# SparkFun_ProtoSnap-LilyTwinkle.net
KiCad netlist of a schematic drawn in EAGLE
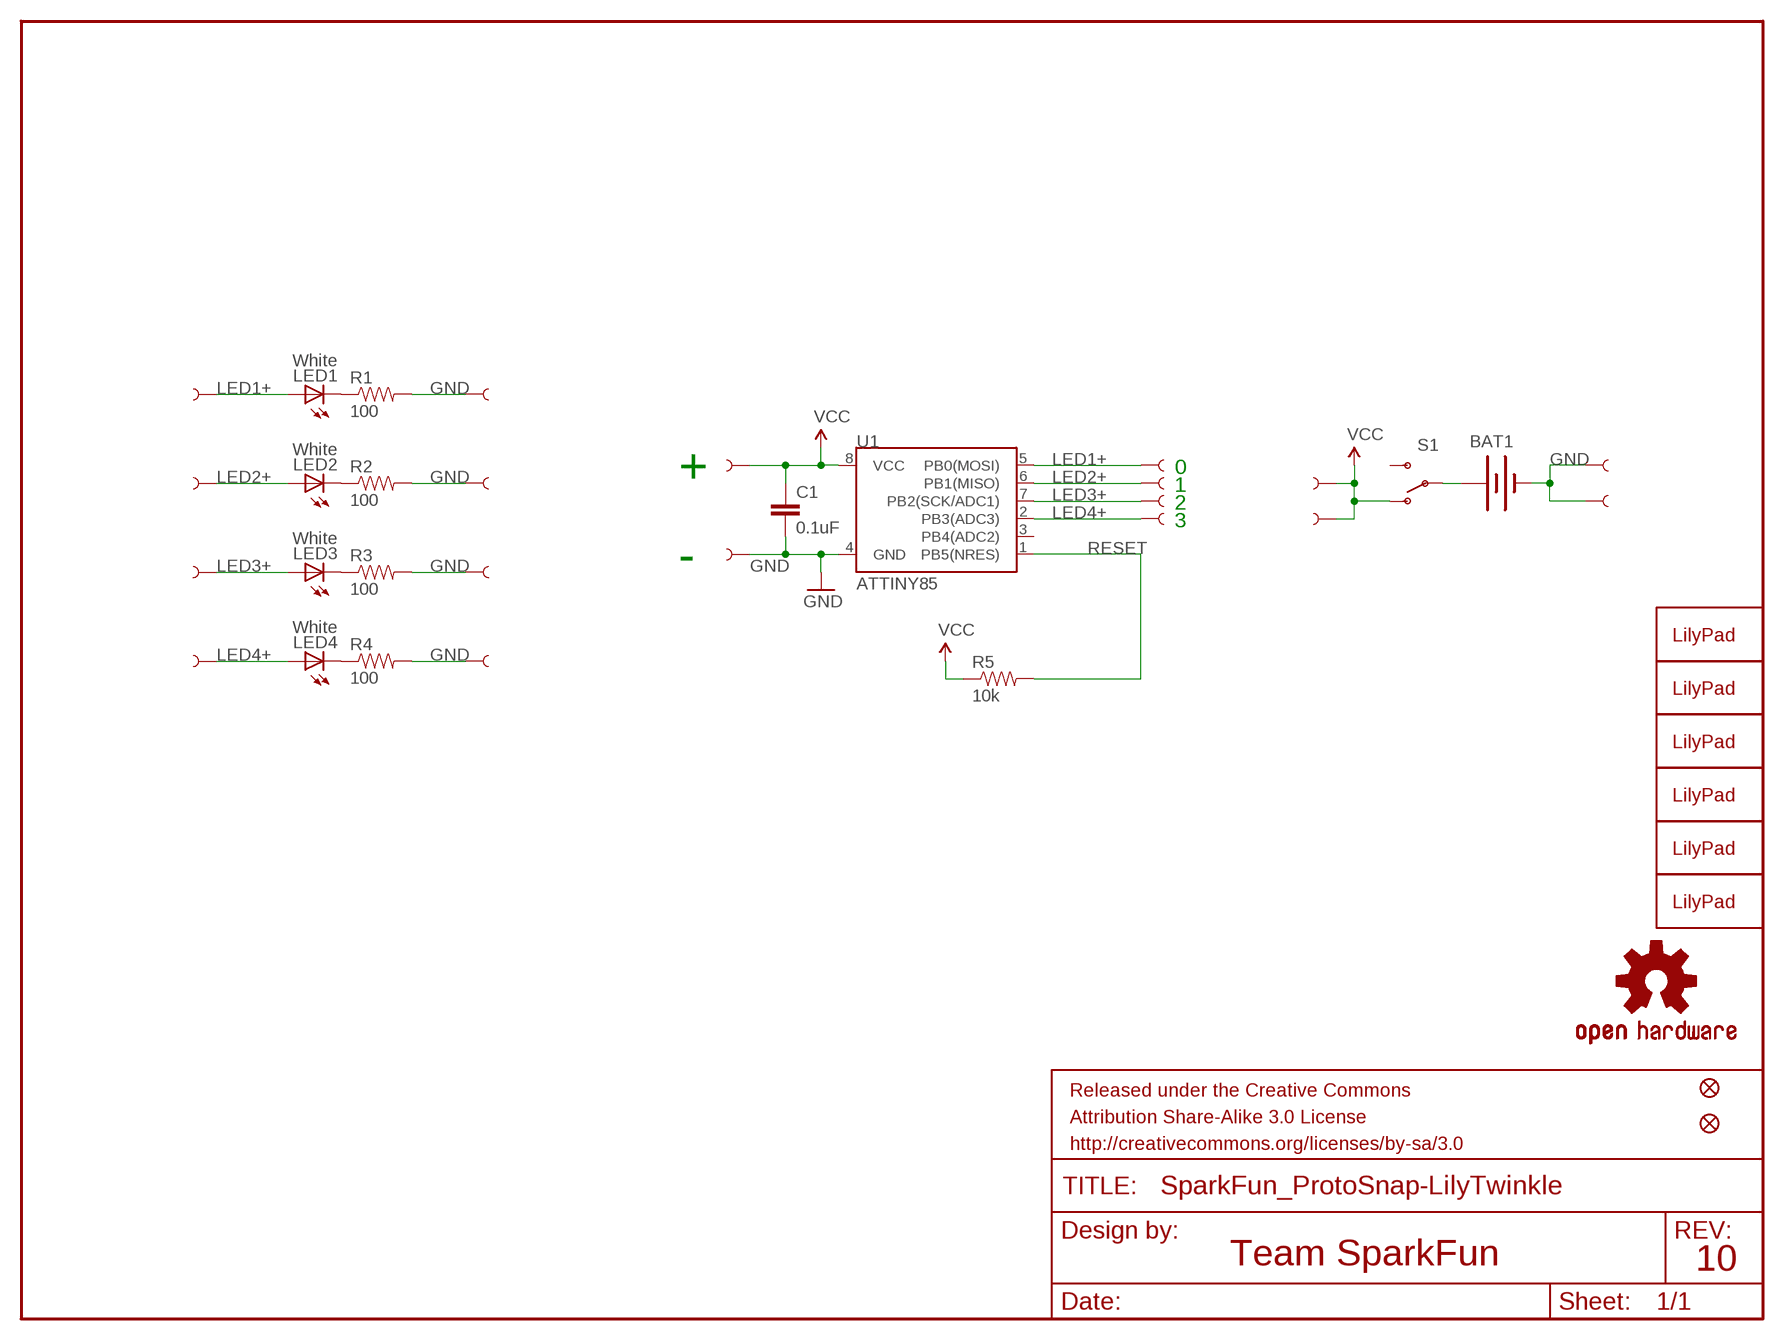
[diagram p0: schematic, sheet 1]

(export (version "E")
  (design (tool "Eeschema 10.0.6"))
  (components
    (comp (ref "1_U$2")
      (value "SEWTAP6")
      (footprint "eagle-import:PETAL-SMALL-2SIDE")
      (libsource (lib "eagle-import") (part "SEWTAP6"))
    )
    (comp (ref "1_U$3")
      (value "SEWTAP6")
      (footprint "eagle-import:PETAL-SMALL-2SIDE")
      (libsource (lib "eagle-import") (part "SEWTAP6"))
    )
    (comp (ref "1_U$4")
      (value "SEWTAP6")
      (footprint "eagle-import:PETAL-SMALL-2SIDE")
      (libsource (lib "eagle-import") (part "SEWTAP6"))
    )
    (comp (ref "1_U$5")
      (value "SEWTAP6")
      (footprint "eagle-import:PETAL-SMALL-2SIDE")
      (libsource (lib "eagle-import") (part "SEWTAP6"))
    )
    (comp (ref "1_U$6")
      (value "SEWTAP6")
      (footprint "eagle-import:PETAL-SMALL-2SIDE")
      (libsource (lib "eagle-import") (part "SEWTAP6"))
    )
    (comp (ref "1_U$7")
      (value "SEWTAP6")
      (footprint "eagle-import:PETAL-SMALL-2SIDE")
      (libsource (lib "eagle-import") (part "SEWTAP6"))
    )
    (comp (ref "3_LED+")
      (value "SEWTAP6")
      (footprint "eagle-import:PETAL-SMALL")
      (libsource (lib "eagle-import") (part "3_LilyPad-Wearables_SEWTAP4"))
    )
    (comp (ref "3_LED-")
      (value "SEWTAP6")
      (footprint "eagle-import:PETAL-SMALL")
      (libsource (lib "eagle-import") (part "SEWTAP2SIDE"))
    )
    (comp (ref "4_LED+")
      (value "SEWTAP6")
      (footprint "eagle-import:PETAL-SMALL")
      (libsource (lib "eagle-import") (part "4_LilyPad-Wearables_SEWTAP4"))
    )
    (comp (ref "4_LED-")
      (value "SEWTAP6")
      (footprint "eagle-import:PETAL-SMALL")
      (libsource (lib "eagle-import") (part "4_LilyPad-Wearables_SEWTAP2SIDE"))
    )
    (comp (ref "5_LED+")
      (value "SEWTAP6")
      (footprint "eagle-import:PETAL-SMALL")
      (libsource (lib "eagle-import") (part "5_LilyPad-Wearables_SEWTAP4"))
    )
    (comp (ref "5_LED-")
      (value "SEWTAP6")
      (footprint "eagle-import:PETAL-SMALL")
      (libsource (lib "eagle-import") (part "5_LilyPad-Wearables_SEWTAP2SIDE"))
    )
    (comp (ref "6_LED+")
      (value "SEWTAP6")
      (footprint "eagle-import:PETAL-SMALL")
      (libsource (lib "eagle-import") (part "6_LilyPad-Wearables_SEWTAP4"))
    )
    (comp (ref "6_LED-")
      (value "SEWTAP6")
      (footprint "eagle-import:PETAL-SMALL")
      (libsource (lib "eagle-import") (part "6_LilyPad-Wearables_SEWTAP2SIDE"))
    )
    (comp (ref "B1+")
      (value "SEWTAP6")
      (footprint "eagle-import:PETAL-SMALL-2SIDE")
      (libsource (lib "eagle-import") (part "2_LilyPad-Wearables_SEWTAP6"))
    )
    (comp (ref "B1-")
      (value "SEWTAP6")
      (footprint "eagle-import:PETAL-SMALL-2SIDE")
      (libsource (lib "eagle-import") (part "2_LilyPad-Wearables_SEWTAP6"))
    )
    (comp (ref "B2+")
      (value "SEWTAP6")
      (footprint "eagle-import:PETAL-SMALL-2SIDE")
      (libsource (lib "eagle-import") (part "2_LilyPad-Wearables_SEWTAP6"))
    )
    (comp (ref "B2-")
      (value "SEWTAP6")
      (footprint "eagle-import:PETAL-SMALL-2SIDE")
      (libsource (lib "eagle-import") (part "2_LilyPad-Wearables_SEWTAP6"))
    )
    (comp (ref "BAT1")
      (value "BATTERY20MM_4LEGS")
      (footprint "eagle-import:BATTCON_20MM_4LEGS")
      (libsource (lib "eagle-import") (part "BATTERY20MM_4LEGS"))
    )
    (comp (ref "BATT_LOGO")
      (value "LOGO-LPLP")
      (footprint "eagle-import:LOGO-LILYPAD")
      (libsource (lib "eagle-import") (part "LOGO-LPLP"))
    )
    (comp (ref "BATT_OHS")
      (value "OSHW-LOGOS")
      (footprint "eagle-import:OSHW-LOGO-S")
      (libsource (lib "eagle-import") (part "OSHW-LOGOS"))
    )
    (comp (ref "C1")
      (value "0.1uF")
      (footprint "eagle-import:0402-CAP")
      (libsource (lib "eagle-import") (part ".1UF-CER"))
    )
    (comp (ref "FRAME1")
      (value "FRAME-LETTER")
      (footprint "eagle-import:CREATIVE_COMMONS")
      (libsource (lib "eagle-import") (part "FRAME-LETTER"))
    )
    (comp (ref "JP1")
      (value "FIDUCIALUFIDUCIAL")
      (footprint "eagle-import:MICRO-FIDUCIAL")
      (libsource (lib "eagle-import") (part "FIDUCIALUFIDUCIAL"))
    )
    (comp (ref "JP2")
      (value "FIDUCIALUFIDUCIAL")
      (footprint "eagle-import:MICRO-FIDUCIAL")
      (libsource (lib "eagle-import") (part "FIDUCIALUFIDUCIAL"))
    )
    (comp (ref "LED1")
      (value "White")
      (footprint "eagle-import:LED-1206")
      (libsource (lib "eagle-import") (part "LED-WHITE"))
    )
    (comp (ref "LED1_LOGO")
      (value "LOGO-LPL")
      (footprint "eagle-import:LOGO-L")
      (libsource (lib "eagle-import") (part "LOGO-LPL"))
    )
    (comp (ref "LED2")
      (value "White")
      (footprint "eagle-import:LED-1206")
      (libsource (lib "eagle-import") (part "LED-WHITE"))
    )
    (comp (ref "LED2_LOGO")
      (value "LOGO-LPL")
      (footprint "eagle-import:LOGO-L")
      (libsource (lib "eagle-import") (part "LOGO-LPL"))
    )
    (comp (ref "LED3")
      (value "White")
      (footprint "eagle-import:LED-1206")
      (libsource (lib "eagle-import") (part "LED-WHITE"))
    )
    (comp (ref "LED3_LOGO")
      (value "LOGO-LPL")
      (footprint "eagle-import:LOGO-L")
      (libsource (lib "eagle-import") (part "LOGO-LPL"))
    )
    (comp (ref "LED4")
      (value "White")
      (footprint "eagle-import:LED-1206")
      (libsource (lib "eagle-import") (part "LED-WHITE"))
    )
    (comp (ref "LED4_LOGO")
      (value "LOGO-LPL")
      (footprint "eagle-import:LOGO-L")
      (libsource (lib "eagle-import") (part "LOGO-LPL"))
    )
    (comp (ref "R1")
      (value "100")
      (footprint "eagle-import:0603-RES")
      (libsource (lib "eagle-import") (part "6_SparkFun_RESISTOR0603-RES"))
    )
    (comp (ref "R2")
      (value "100")
      (footprint "eagle-import:0603-RES")
      (libsource (lib "eagle-import") (part "5_SparkFun_RESISTOR0603-RES"))
    )
    (comp (ref "R3")
      (value "100")
      (footprint "eagle-import:0603-RES")
      (libsource (lib "eagle-import") (part "RESISTOR0603-RES"))
    )
    (comp (ref "R4")
      (value "100")
      (footprint "eagle-import:0603-RES")
      (libsource (lib "eagle-import") (part "4_SparkFun_RESISTOR0603-RES"))
    )
    (comp (ref "R5")
      (value "10k")
      (footprint "eagle-import:0402-RES")
      (libsource (lib "eagle-import") (part "10K-1%RES-00824"))
    )
    (comp (ref "S1")
      (value "SWITCH-SPDTSMD")
      (footprint "eagle-import:AYZ0202")
      (libsource (lib "eagle-import") (part "SWITCH-SPDTSMD"))
    )
    (comp (ref "TINY_LOGO")
      (value "LOGO-LPL")
      (footprint "eagle-import:LOGO-L")
      (libsource (lib "eagle-import") (part "LOGO-LPL"))
    )
    (comp (ref "U1")
      (value "ATTINY85")
      (footprint "eagle-import:SO08-EIAJ")
      (libsource (lib "eagle-import") (part "ATTINY45TINY85-20-SMT"))
    )
  )
  (nets
    (net (code "1") (name "/LED1+") (class "Default")
      (node (ref "1_U$7") (pin "1") (pinfunction "1_1") (pintype "bidirectional"))
      (node (ref "6_LED+") (pin "1") (pinfunction "1_1") (pintype "bidirectional"))
      (node (ref "LED1") (pin "A") (pinfunction "A_A") (pintype "passive"))
      (node (ref "U1") (pin "5") (pinfunction "PB0(MOSI)_5") (pintype "bidirectional"))
    )
    (net (code "2") (name "/LED2+") (class "Default")
      (node (ref "1_U$3") (pin "1") (pinfunction "1_1") (pintype "bidirectional"))
      (node (ref "5_LED+") (pin "1") (pinfunction "1_1") (pintype "bidirectional"))
      (node (ref "LED2") (pin "A") (pinfunction "A_A") (pintype "passive"))
      (node (ref "U1") (pin "6") (pinfunction "PB1(MISO)_6") (pintype "bidirectional"))
    )
    (net (code "3") (name "/LED3+") (class "Default")
      (node (ref "1_U$4") (pin "1") (pinfunction "1_1") (pintype "bidirectional"))
      (node (ref "3_LED+") (pin "1") (pinfunction "1_1") (pintype "bidirectional"))
      (node (ref "LED3") (pin "A") (pinfunction "A_A") (pintype "passive"))
      (node (ref "U1") (pin "7") (pinfunction "PB2(SCK/ADC1)_7") (pintype "bidirectional"))
    )
    (net (code "4") (name "/LED4+") (class "Default")
      (node (ref "1_U$6") (pin "1") (pinfunction "1_1") (pintype "bidirectional"))
      (node (ref "4_LED+") (pin "1") (pinfunction "1_1") (pintype "bidirectional"))
      (node (ref "LED4") (pin "A") (pinfunction "A_A") (pintype "passive"))
      (node (ref "U1") (pin "2") (pinfunction "PB3(ADC3)_2") (pintype "bidirectional"))
    )
    (net (code "5") (name "/RESET") (class "Default")
      (node (ref "R5") (pin "2") (pinfunction "2_2") (pintype "passive"))
      (node (ref "U1") (pin "1") (pinfunction "PB5(NRES)_1") (pintype "bidirectional"))
    )
    (net (code "6") (name "GND") (class "Default")
      (node (ref "1_U$2") (pin "1") (pinfunction "1_1") (pintype "bidirectional"))
      (node (ref "3_LED-") (pin "1") (pinfunction "1_1") (pintype "bidirectional"))
      (node (ref "4_LED-") (pin "1") (pinfunction "1_1") (pintype "bidirectional"))
      (node (ref "5_LED-") (pin "1") (pinfunction "1_1") (pintype "bidirectional"))
      (node (ref "6_LED-") (pin "1") (pinfunction "1_1") (pintype "bidirectional"))
      (node (ref "B1-") (pin "1") (pinfunction "1_1") (pintype "bidirectional"))
      (node (ref "B2-") (pin "1") (pinfunction "1_1") (pintype "bidirectional"))
      (node (ref "BAT1") (pin "2") (pinfunction "-_2") (pintype "power_in"))
      (node (ref "C1") (pin "2") (pinfunction "2_2") (pintype "passive"))
      (node (ref "R1") (pin "2") (pinfunction "2_2") (pintype "passive"))
      (node (ref "R2") (pin "2") (pinfunction "2_2") (pintype "passive"))
      (node (ref "R3") (pin "2") (pinfunction "2_2") (pintype "passive"))
      (node (ref "R4") (pin "2") (pinfunction "2_2") (pintype "passive"))
      (node (ref "U1") (pin "4") (pinfunction "GND_4") (pintype "bidirectional"))
    )
    (net (code "7") (name "Net-(BAT1-+)") (class "Default")
      (node (ref "BAT1") (pin "1") (pinfunction "+_1") (pintype "power_in"))
      (node (ref "S1") (pin "2") (pinfunction "P_2") (pintype "passive"))
    )
    (net (code "8") (name "Net-(LED1-PadC)") (class "Default")
      (node (ref "LED1") (pin "C") (pinfunction "C_C") (pintype "passive"))
      (node (ref "R1") (pin "1") (pinfunction "1_1") (pintype "passive"))
    )
    (net (code "9") (name "Net-(LED2-PadC)") (class "Default")
      (node (ref "LED2") (pin "C") (pinfunction "C_C") (pintype "passive"))
      (node (ref "R2") (pin "1") (pinfunction "1_1") (pintype "passive"))
    )
    (net (code "10") (name "Net-(LED3-PadC)") (class "Default")
      (node (ref "LED3") (pin "C") (pinfunction "C_C") (pintype "passive"))
      (node (ref "R3") (pin "1") (pinfunction "1_1") (pintype "passive"))
    )
    (net (code "11") (name "Net-(LED4-PadC)") (class "Default")
      (node (ref "LED4") (pin "C") (pinfunction "C_C") (pintype "passive"))
      (node (ref "R4") (pin "1") (pinfunction "1_1") (pintype "passive"))
    )
    (net (code "12") (name "VCC") (class "Default")
      (node (ref "1_U$5") (pin "1") (pinfunction "1_1") (pintype "bidirectional"))
      (node (ref "B1+") (pin "1") (pinfunction "1_1") (pintype "bidirectional"))
      (node (ref "B2+") (pin "1") (pinfunction "1_1") (pintype "bidirectional"))
      (node (ref "C1") (pin "1") (pinfunction "1_1") (pintype "passive"))
      (node (ref "R5") (pin "1") (pinfunction "1_1") (pintype "passive"))
      (node (ref "S1") (pin "1") (pinfunction "O_1") (pintype "passive"))
      (node (ref "U1") (pin "8") (pinfunction "VCC_8") (pintype "bidirectional"))
    )
    (net (code "13") (name "unconnected-(S1-S-Pad3)") (class "Default")
      (node (ref "S1") (pin "3") (pinfunction "S_3") (pintype "passive"))
    )
    (net (code "14") (name "unconnected-(U1-PB4(ADC2)-Pad3)") (class "Default")
      (node (ref "U1") (pin "3") (pinfunction "PB4(ADC2)_3") (pintype "bidirectional"))
    )
  )
)
